# keyboard.net
KiCad netlist of a schematic drawn in EAGLE
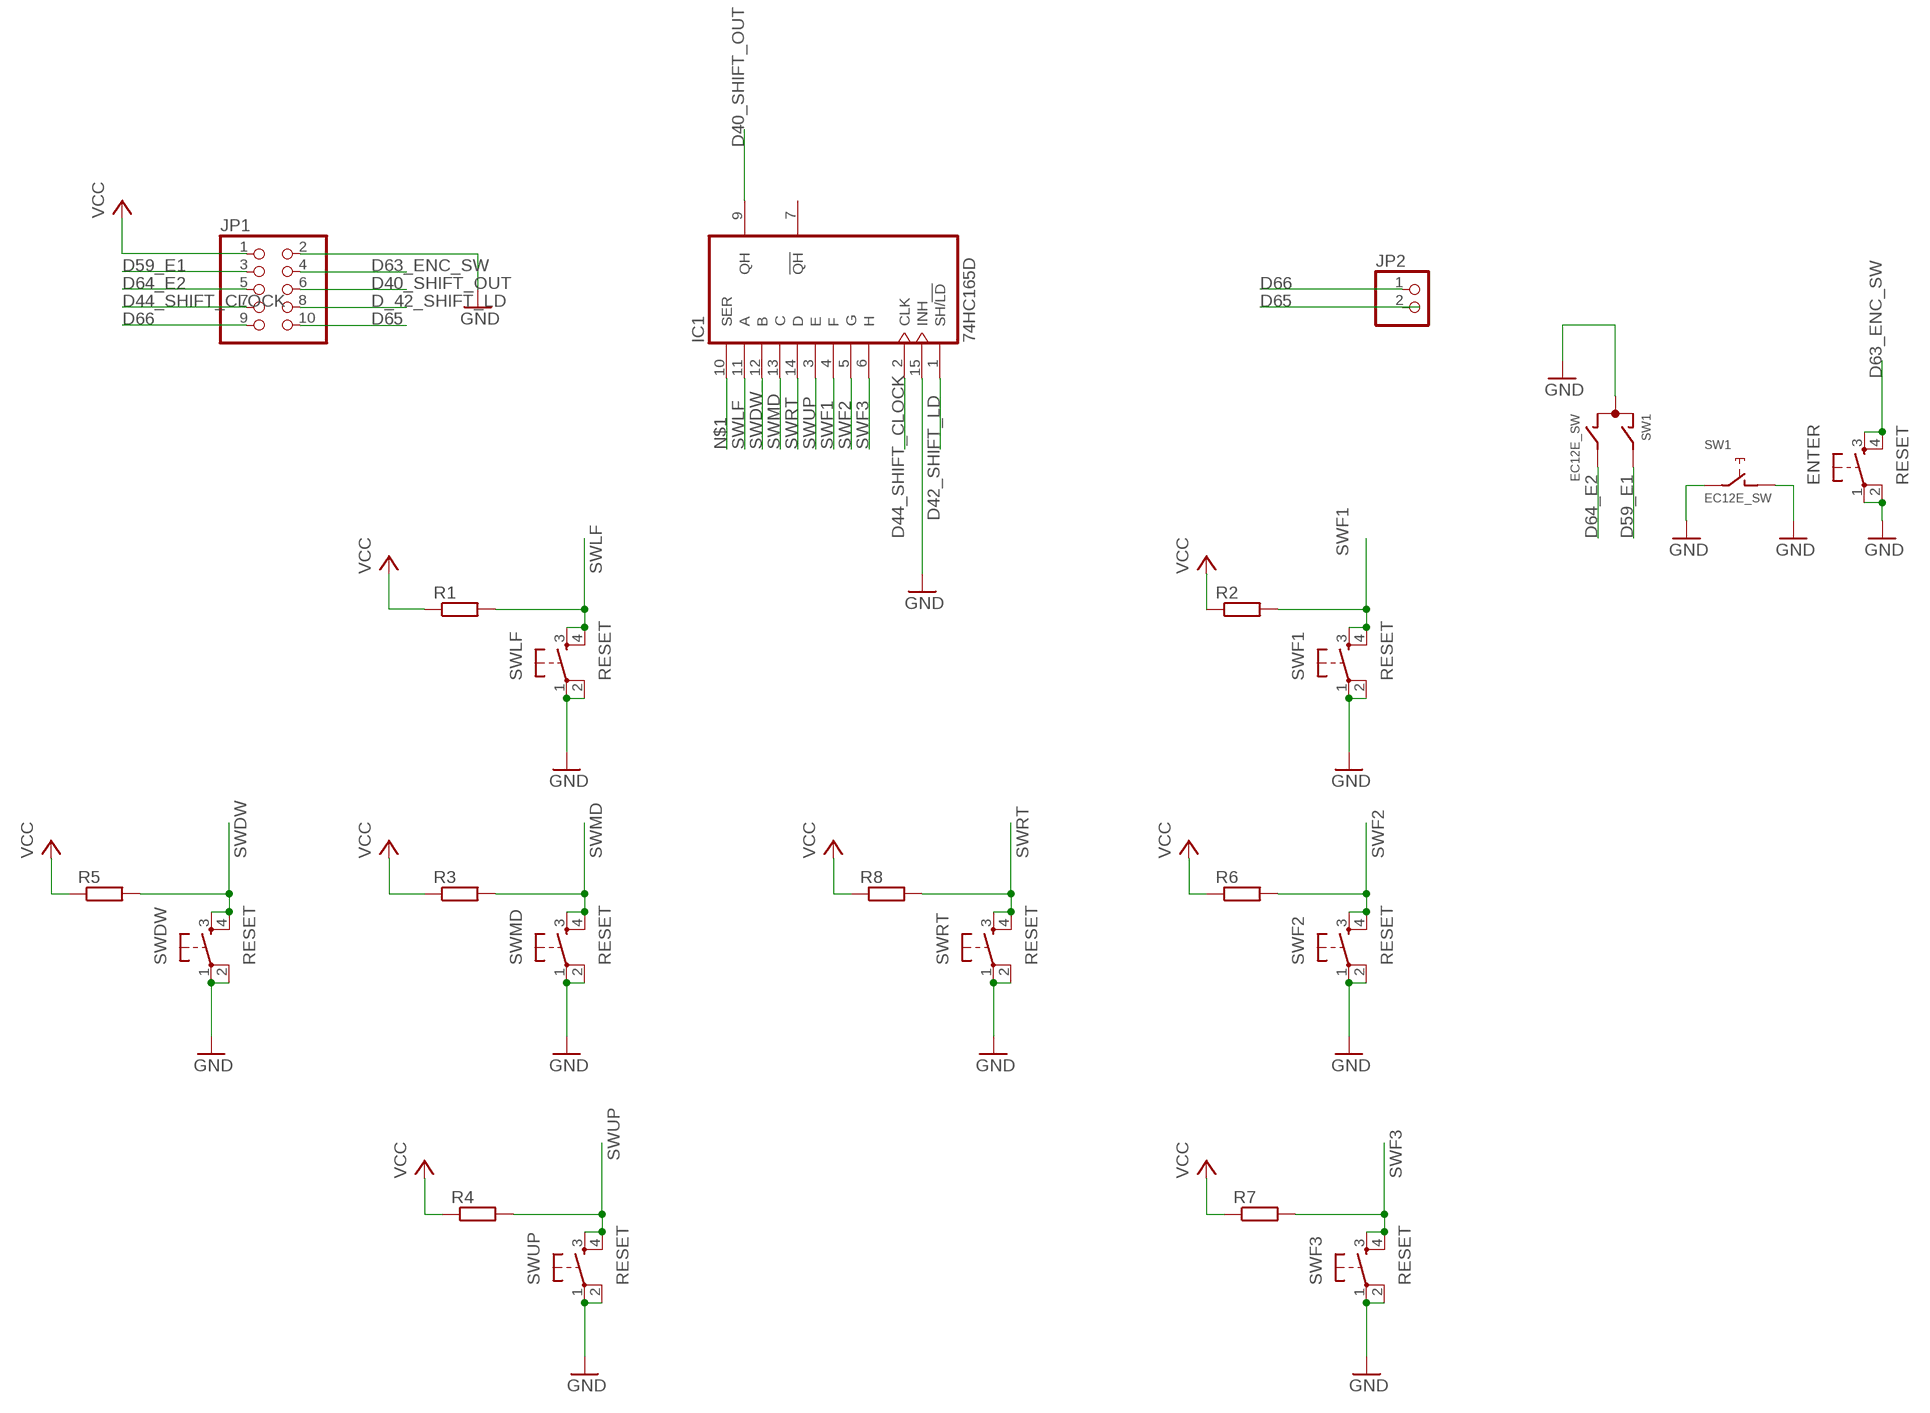
[diagram p0: schematic, sheet 1]

(export (version "E")
  (design (tool "Eeschema 10.0.6"))
  (components
    (comp (ref "ENTER")
      (value "RESET")
      (footprint "eagle-import:TACTILE-PTH")
      (libsource (lib "eagle-import") (part "TAC_SWITCHPTH"))
    )
    (comp (ref "IC1")
      (value "74HC165D")
      (footprint "eagle-import:SO16")
      (libsource (lib "eagle-import") (part "74165DHC"))
    )
    (comp (ref "JP1")
      (value "PINHD-2X5")
      (footprint "eagle-import:2X05")
      (libsource (lib "eagle-import") (part "PINHD-2X5"))
    )
    (comp (ref "JP2")
      (value "PINHD-1X2")
      (footprint "eagle-import:1X02")
      (libsource (lib "eagle-import") (part "PINHD-1X2"))
    )
    (comp (ref "R1")
      (value "R-EU_R0603")
      (footprint "eagle-import:R0603")
      (libsource (lib "eagle-import") (part "R-EU_R0603"))
    )
    (comp (ref "R2")
      (value "R-EU_R0603")
      (footprint "eagle-import:R0603")
      (libsource (lib "eagle-import") (part "R-EU_R0603"))
    )
    (comp (ref "R3")
      (value "R-EU_R0603")
      (footprint "eagle-import:R0603")
      (libsource (lib "eagle-import") (part "R-EU_R0603"))
    )
    (comp (ref "R4")
      (value "R-EU_R0603")
      (footprint "eagle-import:R0603")
      (libsource (lib "eagle-import") (part "R-EU_R0603"))
    )
    (comp (ref "R5")
      (value "R-EU_R0603")
      (footprint "eagle-import:R0603")
      (libsource (lib "eagle-import") (part "R-EU_R0603"))
    )
    (comp (ref "R6")
      (value "R-EU_R0603")
      (footprint "eagle-import:R0603")
      (libsource (lib "eagle-import") (part "R-EU_R0603"))
    )
    (comp (ref "R7")
      (value "R-EU_R0603")
      (footprint "eagle-import:R0603")
      (libsource (lib "eagle-import") (part "R-EU_R0603"))
    )
    (comp (ref "R8")
      (value "R-EU_R0603")
      (footprint "eagle-import:R0603")
      (libsource (lib "eagle-import") (part "R-EU_R0603"))
    )
    (comp (ref "SW1")
      (value "EC12E_SW")
      (footprint "eagle-import:ALPS_EC12E_SW")
      (fields (field (name "MPN") "EC12E2424407"))
      (libsource (lib "eagle-import") (part "EC12E_SW"))
    )
    (comp (ref "SWDW")
      (value "RESET")
      (footprint "eagle-import:TACTILE-PTH")
      (libsource (lib "eagle-import") (part "TAC_SWITCHPTH"))
    )
    (comp (ref "SWF1")
      (value "RESET")
      (footprint "eagle-import:TACTILE-PTH")
      (libsource (lib "eagle-import") (part "TAC_SWITCHPTH"))
    )
    (comp (ref "SWF2")
      (value "RESET")
      (footprint "eagle-import:TACTILE-PTH")
      (libsource (lib "eagle-import") (part "TAC_SWITCHPTH"))
    )
    (comp (ref "SWF3")
      (value "RESET")
      (footprint "eagle-import:TACTILE-PTH")
      (libsource (lib "eagle-import") (part "TAC_SWITCHPTH"))
    )
    (comp (ref "SWLF")
      (value "RESET")
      (footprint "eagle-import:TACTILE-PTH")
      (libsource (lib "eagle-import") (part "TAC_SWITCHPTH"))
    )
    (comp (ref "SWMD")
      (value "RESET")
      (footprint "eagle-import:TACTILE-PTH")
      (libsource (lib "eagle-import") (part "TAC_SWITCHPTH"))
    )
    (comp (ref "SWRT")
      (value "RESET")
      (footprint "eagle-import:TACTILE-PTH")
      (libsource (lib "eagle-import") (part "TAC_SWITCHPTH"))
    )
    (comp (ref "SWUP")
      (value "RESET")
      (footprint "eagle-import:TACTILE-PTH")
      (libsource (lib "eagle-import") (part "TAC_SWITCHPTH"))
    )
  )
  (nets
    (net (code "1") (name "/D40_SHIFT_OUT") (class "Default")
      (node (ref "IC1") (pin "9") (pinfunction "QH_9") (pintype "output"))
      (node (ref "JP1") (pin "6") (pinfunction "6_6") (pintype "passive"))
    )
    (net (code "2") (name "/D42_SHIFT_LD") (class "Default")
      (node (ref "IC1") (pin "1") (pinfunction "SH/~{LD}_1") (pintype "input"))
    )
    (net (code "3") (name "/D44_SHIFT_CLOCK") (class "Default")
      (node (ref "IC1") (pin "2") (pinfunction "CLK_2") (pintype "input"))
      (node (ref "JP1") (pin "7") (pinfunction "7_7") (pintype "passive"))
    )
    (net (code "4") (name "/D59_E1") (class "Default")
      (node (ref "JP1") (pin "3") (pinfunction "3_3") (pintype "passive"))
      (node (ref "SW1") (pin "A") (pinfunction "A_A") (pintype "passive"))
    )
    (net (code "5") (name "/D63_ENC_SW") (class "Default")
      (node (ref "ENTER") (pin "3") (pinfunction "3_3") (pintype "passive"))
      (node (ref "ENTER") (pin "4") (pinfunction "4_4") (pintype "passive"))
      (node (ref "JP1") (pin "4") (pinfunction "4_4") (pintype "passive"))
    )
    (net (code "6") (name "/D64_E2") (class "Default")
      (node (ref "JP1") (pin "5") (pinfunction "5_5") (pintype "passive"))
      (node (ref "SW1") (pin "B") (pinfunction "B_B") (pintype "passive"))
    )
    (net (code "7") (name "/D65") (class "Default")
      (node (ref "JP1") (pin "10") (pinfunction "10_10") (pintype "passive"))
    )
    (net (code "8") (name "/D66") (class "Default")
      (node (ref "JP1") (pin "9") (pinfunction "9_9") (pintype "passive"))
      (node (ref "JP2") (pin "1") (pinfunction "1_1") (pintype "passive"))
    )
    (net (code "9") (name "/D_42_SHIFT_LD") (class "Default")
      (node (ref "JP1") (pin "8") (pinfunction "8_8") (pintype "passive"))
    )
    (net (code "10") (name "/N$1") (class "Default")
      (node (ref "IC1") (pin "10") (pinfunction "SER_10") (pintype "input"))
    )
    (net (code "11") (name "/SWDW") (class "Default")
      (node (ref "IC1") (pin "12") (pinfunction "B_12") (pintype "input"))
      (node (ref "R5") (pin "2") (pinfunction "2_2") (pintype "passive"))
      (node (ref "SWDW") (pin "3") (pinfunction "3_3") (pintype "passive"))
      (node (ref "SWDW") (pin "4") (pinfunction "4_4") (pintype "passive"))
    )
    (net (code "12") (name "/SWF1") (class "Default")
      (node (ref "IC1") (pin "4") (pinfunction "F_4") (pintype "input"))
      (node (ref "R2") (pin "2") (pinfunction "2_2") (pintype "passive"))
      (node (ref "SWF1") (pin "3") (pinfunction "3_3") (pintype "passive"))
      (node (ref "SWF1") (pin "4") (pinfunction "4_4") (pintype "passive"))
    )
    (net (code "13") (name "/SWF2") (class "Default")
      (node (ref "IC1") (pin "5") (pinfunction "G_5") (pintype "input"))
      (node (ref "R6") (pin "2") (pinfunction "2_2") (pintype "passive"))
      (node (ref "SWF2") (pin "3") (pinfunction "3_3") (pintype "passive"))
      (node (ref "SWF2") (pin "4") (pinfunction "4_4") (pintype "passive"))
    )
    (net (code "14") (name "/SWF3") (class "Default")
      (node (ref "IC1") (pin "6") (pinfunction "H_6") (pintype "input"))
      (node (ref "R7") (pin "2") (pinfunction "2_2") (pintype "passive"))
      (node (ref "SWF3") (pin "3") (pinfunction "3_3") (pintype "passive"))
      (node (ref "SWF3") (pin "4") (pinfunction "4_4") (pintype "passive"))
    )
    (net (code "15") (name "/SWLF") (class "Default")
      (node (ref "IC1") (pin "11") (pinfunction "A_11") (pintype "input"))
      (node (ref "R1") (pin "2") (pinfunction "2_2") (pintype "passive"))
      (node (ref "SWLF") (pin "3") (pinfunction "3_3") (pintype "passive"))
      (node (ref "SWLF") (pin "4") (pinfunction "4_4") (pintype "passive"))
    )
    (net (code "16") (name "/SWMD") (class "Default")
      (node (ref "IC1") (pin "13") (pinfunction "C_13") (pintype "input"))
      (node (ref "R3") (pin "2") (pinfunction "2_2") (pintype "passive"))
      (node (ref "SWMD") (pin "3") (pinfunction "3_3") (pintype "passive"))
      (node (ref "SWMD") (pin "4") (pinfunction "4_4") (pintype "passive"))
    )
    (net (code "17") (name "/SWRT") (class "Default")
      (node (ref "IC1") (pin "14") (pinfunction "D_14") (pintype "input"))
      (node (ref "R8") (pin "2") (pinfunction "2_2") (pintype "passive"))
      (node (ref "SWRT") (pin "3") (pinfunction "3_3") (pintype "passive"))
      (node (ref "SWRT") (pin "4") (pinfunction "4_4") (pintype "passive"))
    )
    (net (code "18") (name "/SWUP") (class "Default")
      (node (ref "IC1") (pin "3") (pinfunction "E_3") (pintype "input"))
      (node (ref "R4") (pin "2") (pinfunction "2_2") (pintype "passive"))
      (node (ref "SWUP") (pin "3") (pinfunction "3_3") (pintype "passive"))
      (node (ref "SWUP") (pin "4") (pinfunction "4_4") (pintype "passive"))
    )
    (net (code "19") (name "GND") (class "Default")
      (node (ref "ENTER") (pin "1") (pinfunction "1_1") (pintype "passive"))
      (node (ref "ENTER") (pin "2") (pinfunction "2_2") (pintype "passive"))
      (node (ref "IC1") (pin "15") (pinfunction "INH_15") (pintype "input"))
      (node (ref "JP1") (pin "2") (pinfunction "2_2") (pintype "passive"))
      (node (ref "SW1") (pin "C") (pinfunction "C_C") (pintype "passive"))
      (node (ref "SW1") (pin "D") (pinfunction "1_D") (pintype "passive"))
      (node (ref "SW1") (pin "E") (pinfunction "2_E") (pintype "passive"))
      (node (ref "SWDW") (pin "1") (pinfunction "1_1") (pintype "passive"))
      (node (ref "SWDW") (pin "2") (pinfunction "2_2") (pintype "passive"))
      (node (ref "SWF1") (pin "1") (pinfunction "1_1") (pintype "passive"))
      (node (ref "SWF1") (pin "2") (pinfunction "2_2") (pintype "passive"))
      (node (ref "SWF2") (pin "1") (pinfunction "1_1") (pintype "passive"))
      (node (ref "SWF2") (pin "2") (pinfunction "2_2") (pintype "passive"))
      (node (ref "SWF3") (pin "1") (pinfunction "1_1") (pintype "passive"))
      (node (ref "SWF3") (pin "2") (pinfunction "2_2") (pintype "passive"))
      (node (ref "SWLF") (pin "1") (pinfunction "1_1") (pintype "passive"))
      (node (ref "SWLF") (pin "2") (pinfunction "2_2") (pintype "passive"))
      (node (ref "SWMD") (pin "1") (pinfunction "1_1") (pintype "passive"))
      (node (ref "SWMD") (pin "2") (pinfunction "2_2") (pintype "passive"))
      (node (ref "SWRT") (pin "1") (pinfunction "1_1") (pintype "passive"))
      (node (ref "SWRT") (pin "2") (pinfunction "2_2") (pintype "passive"))
      (node (ref "SWUP") (pin "1") (pinfunction "1_1") (pintype "passive"))
      (node (ref "SWUP") (pin "2") (pinfunction "2_2") (pintype "passive"))
    )
    (net (code "20") (name "VCC") (class "Default")
      (node (ref "JP1") (pin "1") (pinfunction "1_1") (pintype "passive"))
      (node (ref "R1") (pin "1") (pinfunction "1_1") (pintype "passive"))
      (node (ref "R2") (pin "1") (pinfunction "1_1") (pintype "passive"))
      (node (ref "R3") (pin "1") (pinfunction "1_1") (pintype "passive"))
      (node (ref "R4") (pin "1") (pinfunction "1_1") (pintype "passive"))
      (node (ref "R5") (pin "1") (pinfunction "1_1") (pintype "passive"))
      (node (ref "R6") (pin "1") (pinfunction "1_1") (pintype "passive"))
      (node (ref "R7") (pin "1") (pinfunction "1_1") (pintype "passive"))
      (node (ref "R8") (pin "1") (pinfunction "1_1") (pintype "passive"))
    )
    (net (code "21") (name "unconnected-(IC1A-~{QH}-Pad7)") (class "Default")
      (node (ref "IC1") (pin "7") (pinfunction "~{QH}_7") (pintype "output"))
    )
    (net (code "22") (name "unconnected-(JP2-Pad2)") (class "Default")
      (node (ref "JP2") (pin "2") (pinfunction "2_2") (pintype "passive"))
    )
  )
)
